# WIFI_Bluetooth.net
KiCad netlist of a schematic drawn in Altium Designer
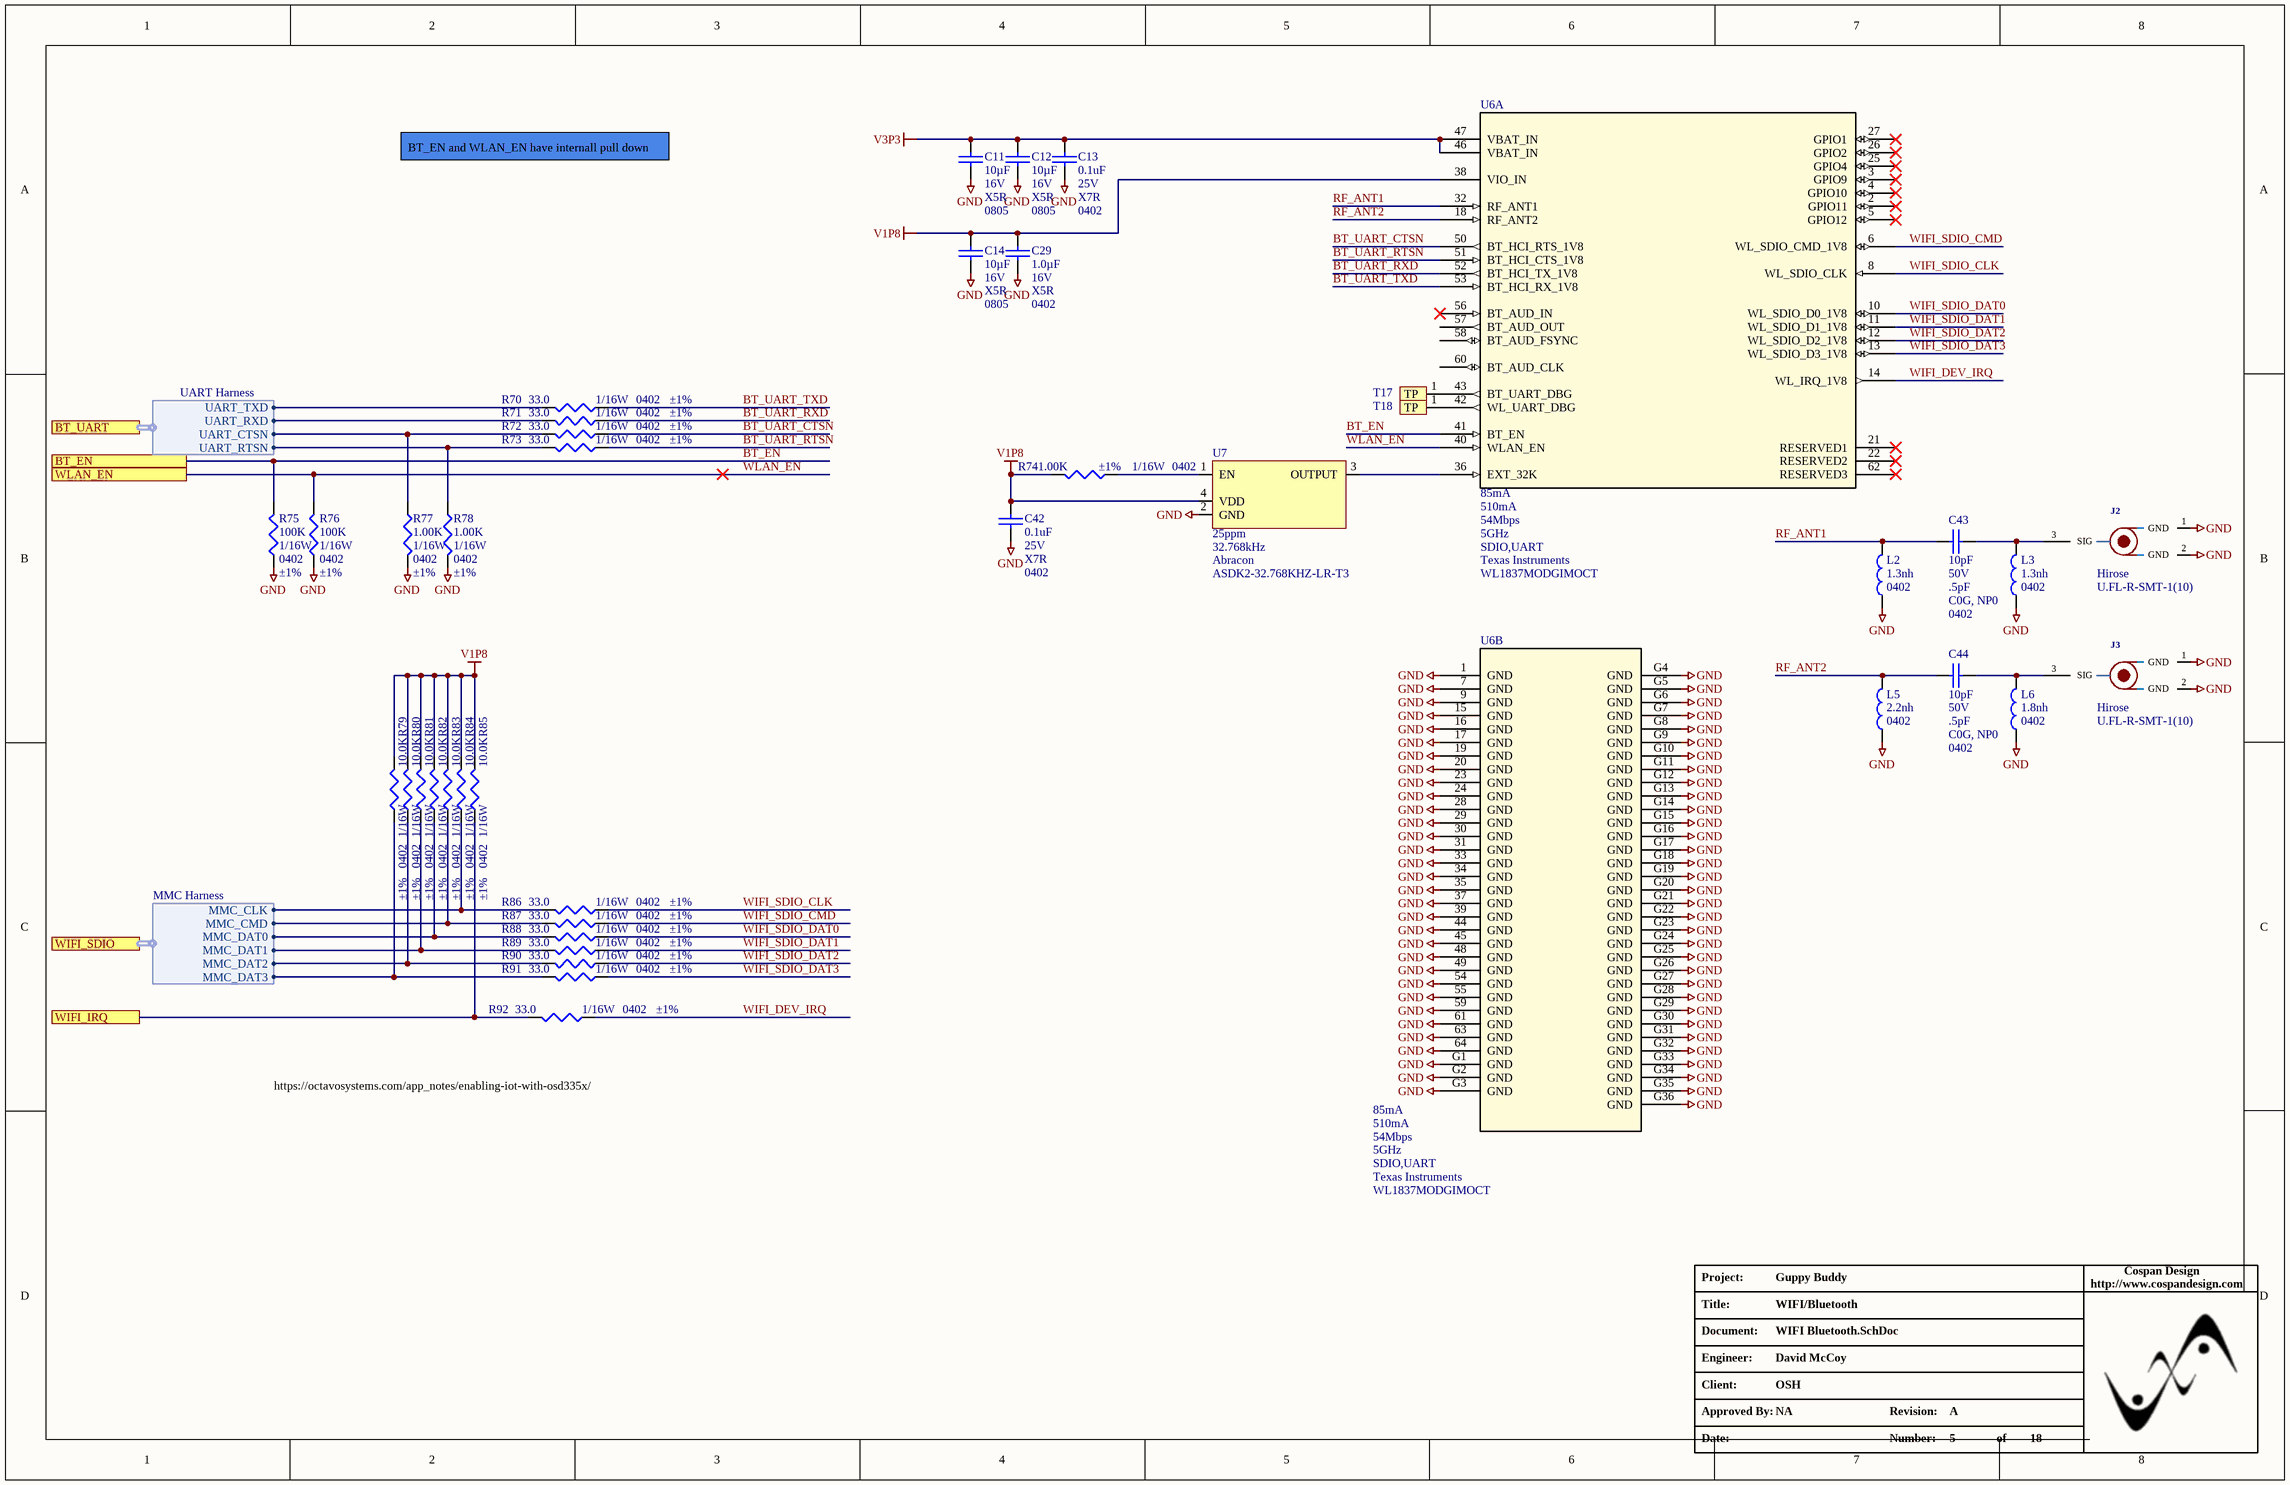
[diagram p0: WIFI Bluetooth.SchDoc]

(export (version "E")
  (design (tool "Eeschema 10.0.6"))
  (components
    (comp (ref "C11")
      (value "10µF")
      (footprint "C_ERA-0805")
      (description "CAP CER 10uF 16V X5R 20% 0805")
      (fields
        (field (name "MANUFACTURER") "Taiyo Yuden")
        (field (name "MANUFACTURER PART NUMBER") "EMK212BJ106KG-T")
        (field (name "CAPACITANCE") "10µF")
        (field (name "VOLTAGE - RATED") "16V")
        (field (name "TEMPERATURE COEFFICIENT") "X5R")
        (field (name "PACKAGE / CASE") "0805")
      )
      (libsource (lib "Main Library") (part "C_0805_10UF_16V"))
    )
    (comp (ref "C12")
      (value "10µF")
      (footprint "C_ERA-0805")
      (description "CAP CER 10uF 16V X5R 20% 0805")
      (fields
        (field (name "MANUFACTURER") "Taiyo Yuden")
        (field (name "MANUFACTURER PART NUMBER") "EMK212BJ106KG-T")
        (field (name "CAPACITANCE") "10µF")
        (field (name "VOLTAGE - RATED") "16V")
        (field (name "TEMPERATURE COEFFICIENT") "X5R")
        (field (name "PACKAGE / CASE") "0805")
      )
      (libsource (lib "Main Library") (part "C_0805_10UF_16V"))
    )
    (comp (ref "C13")
      (value "C_0402_0.1UF_25V")
      (footprint "C_0402")
      (description "CAP CER 0.1UF 25V X6S 0402")
      (fields
        (field (name "TOLERANCE") "10%")
        (field (name "CAPACITANCE") "0.1uF")
        (field (name "VOLTAGE - RATED") "25V")
        (field (name "TEMPERATURE COEFFICIENT") "X7R")
        (field (name "PACKAGE / CASE") "0402")
      )
      (libsource (lib "Cospan Design") (part "C_0402_0.1UF_25V"))
    )
    (comp (ref "C14")
      (value "10µF")
      (footprint "C_ERA-0805")
      (description "CAP CER 10uF 16V X5R 20% 0805")
      (fields
        (field (name "MANUFACTURER") "Taiyo Yuden")
        (field (name "MANUFACTURER PART NUMBER") "EMK212BJ106KG-T")
        (field (name "CAPACITANCE") "10µF")
        (field (name "VOLTAGE - RATED") "16V")
        (field (name "TEMPERATURE COEFFICIENT") "X5R")
        (field (name "PACKAGE / CASE") "0805")
      )
      (libsource (lib "Main Library") (part "C_0805_10UF_16V"))
    )
    (comp (ref "C29")
      (value "1.0uF")
      (footprint "C_0402")
      (description "CAP CER 1.0UF 16V X5R 0402")
      (fields
        (field (name "TOLERANCE") "10%")
        (field (name "CAPACITANCE") "1.0µF")
        (field (name "VOLTAGE - RATED") "16V")
        (field (name "TEMPERATURE COEFFICIENT") "X5R")
        (field (name "PACKAGE / CASE") "0402")
        (field (name "VOLTAGE") "16V")
      )
      (libsource (lib "Main LibraryX") (part "C_0402_1.0UF_16V"))
    )
    (comp (ref "C42")
      (value "C_0402_0.1UF_25V")
      (footprint "C_0402")
      (description "CAP CER 0.1UF 25V X6S 0402")
      (fields
        (field (name "TOLERANCE") "10%")
        (field (name "CAPACITANCE") "0.1uF")
        (field (name "VOLTAGE - RATED") "25V")
        (field (name "TEMPERATURE COEFFICIENT") "X7R")
        (field (name "PACKAGE / CASE") "0402")
      )
      (libsource (lib "Cospan Design") (part "C_0402_0.1UF_25V"))
    )
    (comp (ref "C43")
      (value "10pF")
      (footprint "C_0402")
      (description "CAP CER 10PF 50V NP0 0402")
      (fields
        (field (name "MANUFACTURER") "Taiyo Yuden")
        (field (name "MANUFACTURER PART NUMBER") "UMK105CG100DV-F")
        (field (name "CAPACITANCE") "10pF")
        (field (name "VOLTAGE - RATED") "50V")
        (field (name "TOLERANCE") ".5pF")
        (field (name "TEMPERATURE COEFFICIENT") "C0G, NP0")
        (field (name "PACKAGE / CASE") "0402")
      )
      (libsource (lib "Main Library") (part "C_0402_10PF_50V"))
    )
    (comp (ref "C44")
      (value "10pF")
      (footprint "C_ERA-0402")
      (description "CAP CER 10PF 50V NP0 0402")
      (fields
        (field (name "MANUFACTURER") "Taiyo Yuden")
        (field (name "MANUFACTURER PART NUMBER") "UMK105CG100DV-F")
        (field (name "CAPACITANCE") "10pF")
        (field (name "VOLTAGE - RATED") "50V")
        (field (name "TOLERANCE") ".5pF")
        (field (name "TEMPERATURE COEFFICIENT") "C0G, NP0")
        (field (name "PACKAGE / CASE") "0402")
      )
      (libsource (lib "Main Library") (part "C_0402_10PF_50V"))
    )
    (comp (ref "J2")
      (value "U.FL-R-SMT-1(10)")
      (footprint "U.FL-R-SMT-1")
      (description "CONN UMC JACK STR 50 OHM SMD")
      (fields
        (field (name "MANUFACTURER 1") "Hirose")
        (field (name "MANUFACTURER PART NUMBER 1") "U.FL-R-SMT-1(10)")
        (field (name "LIBRARYNAME") "GHI-Connectors")
      )
      (libsource (lib "Cospan Design") (part "J_U.FL-R-SMT-1"))
    )
    (comp (ref "J3")
      (value "U.FL-R-SMT-1(10)")
      (footprint "U.FL-R-SMT-1")
      (description "CONN UMC JACK STR 50 OHM SMD")
      (fields
        (field (name "MANUFACTURER 1") "Hirose")
        (field (name "MANUFACTURER PART NUMBER 1") "U.FL-R-SMT-1(10)")
        (field (name "LIBRARYNAME") "GHI-Connectors")
      )
      (libsource (lib "Cospan Design") (part "J_U.FL-R-SMT-1"))
    )
    (comp (ref "L2")
      (value "L_0402_1.3nH")
      (footprint "R_0402")
      (description "FIXED IND 1.3NH 1A 90 MOHM")
      (fields
        (field (name "TOLERANCE") "5%")
        (field (name "INDUCTANCE") "1.3nh")
        (field (name "CASE CODE (IMPERIAL)") "0402")
      )
      (libsource (lib "Cospan Design") (part "L_0402_1.3nH"))
    )
    (comp (ref "L3")
      (value "L_0402_1.3nH")
      (footprint "R_0402")
      (description "FIXED IND 1.3NH 1A 90 MOHM")
      (fields
        (field (name "TOLERANCE") "5%")
        (field (name "INDUCTANCE") "1.3nh")
        (field (name "CASE CODE (IMPERIAL)") "0402")
      )
      (libsource (lib "Cospan Design") (part "L_0402_1.3nH"))
    )
    (comp (ref "L5")
      (value "L_0402_2.2nH")
      (footprint "R_0402")
      (description "FIXED IND 2.2NH 950MA 150 MOHM")
      (fields (field (name "INDUCTANCE") "2.2nh") (field (name "CASE CODE (IMPERIAL)") "0402"))
      (libsource (lib "Cospan Design") (part "L_0402_2.2nH"))
    )
    (comp (ref "L6")
      (value "L_0402_1.8nH")
      (footprint "R_0402")
      (description "FIXED IND 1.8NH 950MA 100 MOHM")
      (fields (field (name "INDUCTANCE") "1.8nh") (field (name "CASE CODE (IMPERIAL)") "0402"))
      (libsource (lib "Cospan Design") (part "L_0402_1.8nH"))
    )
    (comp (ref "R70")
      (value "R_0402_33")
      (footprint "R_0402")
      (description "RES 33.0 OHM 1/16W 1% 0402 SMD")
      (fields
        (field (name "MANUFACTURER") "Yageo")
        (field (name "MANUFACTURER PART NUMBER") "RC0402FR-0733RL")
        (field (name "RESISTANCE IN OHMS") "33.0")
        (field (name "POWER (WATTS)") "1/16W")
        (field (name "CASE") "0402")
        (field (name "TOLERANCE") "±1%")
      )
      (libsource (lib "Main Library") (part "R_0402_33"))
    )
    (comp (ref "R71")
      (value "R_0402_33")
      (footprint "R_0402")
      (description "RES 33.0 OHM 1/16W 1% 0402 SMD")
      (fields
        (field (name "MANUFACTURER") "Yageo")
        (field (name "MANUFACTURER PART NUMBER") "RC0402FR-0733RL")
        (field (name "RESISTANCE IN OHMS") "33.0")
        (field (name "POWER (WATTS)") "1/16W")
        (field (name "CASE") "0402")
        (field (name "TOLERANCE") "±1%")
      )
      (libsource (lib "Main Library") (part "R_0402_33"))
    )
    (comp (ref "R72")
      (value "R_0402_33")
      (footprint "R_0402")
      (description "RES 33.0 OHM 1/16W 1% 0402 SMD")
      (fields
        (field (name "MANUFACTURER") "Yageo")
        (field (name "MANUFACTURER PART NUMBER") "RC0402FR-0733RL")
        (field (name "RESISTANCE IN OHMS") "33.0")
        (field (name "POWER (WATTS)") "1/16W")
        (field (name "CASE") "0402")
        (field (name "TOLERANCE") "±1%")
      )
      (libsource (lib "Main Library") (part "R_0402_33"))
    )
    (comp (ref "R73")
      (value "R_0402_33")
      (footprint "R_0402")
      (description "RES 33.0 OHM 1/16W 1% 0402 SMD")
      (fields
        (field (name "MANUFACTURER") "Yageo")
        (field (name "MANUFACTURER PART NUMBER") "RC0402FR-0733RL")
        (field (name "RESISTANCE IN OHMS") "33.0")
        (field (name "POWER (WATTS)") "1/16W")
        (field (name "CASE") "0402")
        (field (name "TOLERANCE") "±1%")
      )
      (libsource (lib "Main Library") (part "R_0402_33"))
    )
    (comp (ref "R74")
      (value "1.0k Ohms")
      (footprint "R_0402")
      (description "RES 1.00K OHM 1/16W 1% 0402 SMD")
      (fields
        (field (name "MANUFACTURER") "Yageo")
        (field (name "MANUFACTURER PART NUMBER") "RC0402FR-071KL")
        (field (name "RESISTANCE IN OHMS") "1.00K")
        (field (name "POWER (WATTS)") "1/16W")
        (field (name "CASE") "0402")
        (field (name "TOLERANCE") "±1%")
      )
      (libsource (lib "Main Library") (part "R_0402_1.0K"))
    )
    (comp (ref "R75")
      (value "R_0402_100.0K")
      (footprint "R_0402")
      (description "RES 100K OHM 1/16W 1% 0402 SMD")
      (fields
        (field (name "MANUFACTURER") "Stackpole Electronics Inc")
        (field (name "MANUFACTURER PART NUMBER") "RMCF0402FT100K")
        (field (name "RESISTANCE IN OHMS") "100K")
        (field (name "POWER (WATTS)") "1/16W")
        (field (name "CASE") "0402")
        (field (name "TOLERANCE") "±1%")
      )
      (libsource (lib "Main Library") (part "R_0402_100.0K"))
    )
    (comp (ref "R76")
      (value "R_0402_100.0K")
      (footprint "R_0402")
      (description "RES 100K OHM 1/16W 1% 0402 SMD")
      (fields
        (field (name "MANUFACTURER") "Stackpole Electronics Inc")
        (field (name "MANUFACTURER PART NUMBER") "RMCF0402FT100K")
        (field (name "RESISTANCE IN OHMS") "100K")
        (field (name "POWER (WATTS)") "1/16W")
        (field (name "CASE") "0402")
        (field (name "TOLERANCE") "±1%")
      )
      (libsource (lib "Main Library") (part "R_0402_100.0K"))
    )
    (comp (ref "R77")
      (value "1.0k Ohms")
      (footprint "R_0402")
      (description "RES 1.00K OHM 1/16W 1% 0402 SMD")
      (fields
        (field (name "MANUFACTURER") "Yageo")
        (field (name "MANUFACTURER PART NUMBER") "RC0402FR-071KL")
        (field (name "RESISTANCE IN OHMS") "1.00K")
        (field (name "POWER (WATTS)") "1/16W")
        (field (name "CASE") "0402")
        (field (name "TOLERANCE") "±1%")
      )
      (libsource (lib "Main Library") (part "R_0402_1.0K"))
    )
    (comp (ref "R78")
      (value "1.0k Ohms")
      (footprint "R_0402")
      (description "RES 1.00K OHM 1/16W 1% 0402 SMD")
      (fields
        (field (name "MANUFACTURER") "Yageo")
        (field (name "MANUFACTURER PART NUMBER") "RC0402FR-071KL")
        (field (name "RESISTANCE IN OHMS") "1.00K")
        (field (name "POWER (WATTS)") "1/16W")
        (field (name "CASE") "0402")
        (field (name "TOLERANCE") "±1%")
      )
      (libsource (lib "Main Library") (part "R_0402_1.0K"))
    )
    (comp (ref "R79")
      (value "R_0402_10.0K")
      (footprint "R_0402")
      (description "RES 10.0K OHM 1/16W 1% 0402 SMD")
      (fields
        (field (name "MANUFACTURER") "Stackpole Electronics Inc")
        (field (name "MANUFACTURER PART NUMBER") "RMCF0402FT10K0")
        (field (name "RESISTANCE IN OHMS") "10.0K")
        (field (name "POWER (WATTS)") "1/16W")
        (field (name "CASE") "0402")
        (field (name "TOLERANCE") "±1%")
      )
      (libsource (lib "Cospan Design") (part "R_0402_10.0K"))
    )
    (comp (ref "R80")
      (value "R_0402_10.0K")
      (footprint "R_0402")
      (description "RES 10.0K OHM 1/16W 1% 0402 SMD")
      (fields
        (field (name "MANUFACTURER") "Stackpole Electronics Inc")
        (field (name "MANUFACTURER PART NUMBER") "RMCF0402FT10K0")
        (field (name "RESISTANCE IN OHMS") "10.0K")
        (field (name "POWER (WATTS)") "1/16W")
        (field (name "CASE") "0402")
        (field (name "TOLERANCE") "±1%")
      )
      (libsource (lib "Cospan Design") (part "R_0402_10.0K"))
    )
    (comp (ref "R81")
      (value "R_0402_10.0K")
      (footprint "R_0402")
      (description "RES 10.0K OHM 1/16W 1% 0402 SMD")
      (fields
        (field (name "MANUFACTURER") "Stackpole Electronics Inc")
        (field (name "MANUFACTURER PART NUMBER") "RMCF0402FT10K0")
        (field (name "RESISTANCE IN OHMS") "10.0K")
        (field (name "POWER (WATTS)") "1/16W")
        (field (name "CASE") "0402")
        (field (name "TOLERANCE") "±1%")
      )
      (libsource (lib "Cospan Design") (part "R_0402_10.0K"))
    )
    (comp (ref "R82")
      (value "R_0402_10.0K")
      (footprint "R_0402")
      (description "RES 10.0K OHM 1/16W 1% 0402 SMD")
      (fields
        (field (name "MANUFACTURER") "Stackpole Electronics Inc")
        (field (name "MANUFACTURER PART NUMBER") "RMCF0402FT10K0")
        (field (name "RESISTANCE IN OHMS") "10.0K")
        (field (name "POWER (WATTS)") "1/16W")
        (field (name "CASE") "0402")
        (field (name "TOLERANCE") "±1%")
      )
      (libsource (lib "Cospan Design") (part "R_0402_10.0K"))
    )
    (comp (ref "R83")
      (value "R_0402_10.0K")
      (footprint "R_0402")
      (description "RES 10.0K OHM 1/16W 1% 0402 SMD")
      (fields
        (field (name "MANUFACTURER") "Stackpole Electronics Inc")
        (field (name "MANUFACTURER PART NUMBER") "RMCF0402FT10K0")
        (field (name "RESISTANCE IN OHMS") "10.0K")
        (field (name "POWER (WATTS)") "1/16W")
        (field (name "CASE") "0402")
        (field (name "TOLERANCE") "±1%")
      )
      (libsource (lib "Cospan Design") (part "R_0402_10.0K"))
    )
    (comp (ref "R84")
      (value "R_0402_10.0K")
      (footprint "R_0402")
      (description "RES 10.0K OHM 1/16W 1% 0402 SMD")
      (fields
        (field (name "MANUFACTURER") "Stackpole Electronics Inc")
        (field (name "MANUFACTURER PART NUMBER") "RMCF0402FT10K0")
        (field (name "RESISTANCE IN OHMS") "10.0K")
        (field (name "POWER (WATTS)") "1/16W")
        (field (name "CASE") "0402")
        (field (name "TOLERANCE") "±1%")
      )
      (libsource (lib "Cospan Design") (part "R_0402_10.0K"))
    )
    (comp (ref "R85")
      (value "R_0402_10.0K")
      (footprint "R_0402")
      (description "RES 10.0K OHM 1/16W 1% 0402 SMD")
      (fields
        (field (name "MANUFACTURER") "Stackpole Electronics Inc")
        (field (name "MANUFACTURER PART NUMBER") "RMCF0402FT10K0")
        (field (name "RESISTANCE IN OHMS") "10.0K")
        (field (name "POWER (WATTS)") "1/16W")
        (field (name "CASE") "0402")
        (field (name "TOLERANCE") "±1%")
      )
      (libsource (lib "Cospan Design") (part "R_0402_10.0K"))
    )
    (comp (ref "R86")
      (value "R_0402_33")
      (footprint "R_0402")
      (description "RES 33.0 OHM 1/16W 1% 0402 SMD")
      (fields
        (field (name "MANUFACTURER") "Yageo")
        (field (name "MANUFACTURER PART NUMBER") "RC0402FR-0733RL")
        (field (name "RESISTANCE IN OHMS") "33.0")
        (field (name "POWER (WATTS)") "1/16W")
        (field (name "CASE") "0402")
        (field (name "TOLERANCE") "±1%")
      )
      (libsource (lib "Main Library") (part "R_0402_33"))
    )
    (comp (ref "R87")
      (value "R_0402_33")
      (footprint "R_0402")
      (description "RES 33.0 OHM 1/16W 1% 0402 SMD")
      (fields
        (field (name "MANUFACTURER") "Yageo")
        (field (name "MANUFACTURER PART NUMBER") "RC0402FR-0733RL")
        (field (name "RESISTANCE IN OHMS") "33.0")
        (field (name "POWER (WATTS)") "1/16W")
        (field (name "CASE") "0402")
        (field (name "TOLERANCE") "±1%")
      )
      (libsource (lib "Main Library") (part "R_0402_33"))
    )
    (comp (ref "R88")
      (value "R_0402_33")
      (footprint "R_0402")
      (description "RES 33.0 OHM 1/16W 1% 0402 SMD")
      (fields
        (field (name "MANUFACTURER") "Yageo")
        (field (name "MANUFACTURER PART NUMBER") "RC0402FR-0733RL")
        (field (name "RESISTANCE IN OHMS") "33.0")
        (field (name "POWER (WATTS)") "1/16W")
        (field (name "CASE") "0402")
        (field (name "TOLERANCE") "±1%")
      )
      (libsource (lib "Main Library") (part "R_0402_33"))
    )
    (comp (ref "R89")
      (value "R_0402_33")
      (footprint "R_0402")
      (description "RES 33.0 OHM 1/16W 1% 0402 SMD")
      (fields
        (field (name "MANUFACTURER") "Yageo")
        (field (name "MANUFACTURER PART NUMBER") "RC0402FR-0733RL")
        (field (name "RESISTANCE IN OHMS") "33.0")
        (field (name "POWER (WATTS)") "1/16W")
        (field (name "CASE") "0402")
        (field (name "TOLERANCE") "±1%")
      )
      (libsource (lib "Main Library") (part "R_0402_33"))
    )
    (comp (ref "R90")
      (value "R_0402_33")
      (footprint "R_0402")
      (description "RES 33.0 OHM 1/16W 1% 0402 SMD")
      (fields
        (field (name "MANUFACTURER") "Yageo")
        (field (name "MANUFACTURER PART NUMBER") "RC0402FR-0733RL")
        (field (name "RESISTANCE IN OHMS") "33.0")
        (field (name "POWER (WATTS)") "1/16W")
        (field (name "CASE") "0402")
        (field (name "TOLERANCE") "±1%")
      )
      (libsource (lib "Main Library") (part "R_0402_33"))
    )
    (comp (ref "R91")
      (value "R_0402_33")
      (footprint "R_0402")
      (description "RES 33.0 OHM 1/16W 1% 0402 SMD")
      (fields
        (field (name "MANUFACTURER") "Yageo")
        (field (name "MANUFACTURER PART NUMBER") "RC0402FR-0733RL")
        (field (name "RESISTANCE IN OHMS") "33.0")
        (field (name "POWER (WATTS)") "1/16W")
        (field (name "CASE") "0402")
        (field (name "TOLERANCE") "±1%")
      )
      (libsource (lib "Main Library") (part "R_0402_33"))
    )
    (comp (ref "R92")
      (value "R_0402_33")
      (footprint "R_0402")
      (description "RES 33.0 OHM 1/16W 1% 0402 SMD")
      (fields
        (field (name "MANUFACTURER") "Yageo")
        (field (name "MANUFACTURER PART NUMBER") "RC0402FR-0733RL")
        (field (name "RESISTANCE IN OHMS") "33.0")
        (field (name "POWER (WATTS)") "1/16W")
        (field (name "CASE") "0402")
        (field (name "TOLERANCE") "±1%")
      )
      (libsource (lib "Main Library") (part "R_0402_33"))
    )
    (comp (ref "T17")
      (value "TEST_POINT_SMALL")
      (footprint "TestPointSmall")
      (description "OSCILLOSCOPE TEST POINT")
      (libsource (lib "Main LibraryX") (part "TEST_POINT_SMALL"))
    )
    (comp (ref "T18")
      (value "TEST_POINT_SMALL")
      (footprint "TestPointSmall")
      (description "OSCILLOSCOPE TEST POINT")
      (libsource (lib "Main LibraryX") (part "TEST_POINT_SMALL"))
    )
    (comp (ref "U6")
      (value "U_WL1837MODGIMOCT")
      (footprint "MOC0100A")
      (description "WiLink Wi-Fi 2.4/5GHz MIMO BT/BLE")
      (fields
        (field (name "CURRENT - RECEIVING") "85mA")
        (field (name "CURRENT - TRANSMITTING") "510mA")
        (field (name "DATA RATE") "54Mbps")
        (field (name "FREQUENCY") "5GHz")
        (field (name "INTERFACE") "SDIO,UART")
        (field (name "MANUFACTURER 1") "Texas Instruments")
        (field (name "MANUFACTURER PART NUMBER 1") "WL1837MODGIMOCT")
      )
      (libsource (lib "Cospan Design") (part "U_WL1837MODGIMOCT"))
    )
    (comp (ref "U7")
      (value "U_ASDK2-32.768KHZ-LR-T3")
      (footprint "KC2520B")
      (description "32.768kHz CMOS XO (Standard) Oscillator Surface Mount 1.8V 1.5mA Enable/Disable")
      (fields
        (field (name "FREQUENCY STABILITY") "25ppm")
        (field (name "FREQUENCY") "32.768kHz")
        (field (name "MANUFACTURER 1") "Abracon")
        (field (name "MANUFACTURER PART NUMBER 1") "ASDK2-32.768KHZ-LR-T3")
      )
      (libsource (lib "Cospan Design") (part "U_ASDK2-32.768KHZ-LR-T3"))
    )
  )
  (nets
    (net (code "4") (name "/BT_EN") (class "Default")
      (node (ref "R75") (pin "1") (pinfunction "1_1") (pintype "passive"))
      (node (ref "U6") (pin "41") (pinfunction "BT_EN_41") (pintype "input"))
    )
    (net (code "5") (name "/BT_UART_CTSN") (class "Default")
      (node (ref "R72") (pin "2") (pinfunction "2_2") (pintype "passive"))
      (node (ref "U6") (pin "50") (pinfunction "BT_HCI_RTS_1V8_50") (pintype "output"))
    )
    (net (code "6") (name "/BT_UART_RTSN") (class "Default")
      (node (ref "R73") (pin "2") (pinfunction "2_2") (pintype "passive"))
      (node (ref "U6") (pin "51") (pinfunction "BT_HCI_CTS_1V8_51") (pintype "input"))
    )
    (net (code "7") (name "/BT_UART_RXD") (class "Default")
      (node (ref "R71") (pin "2") (pinfunction "2_2") (pintype "passive"))
      (node (ref "U6") (pin "52") (pinfunction "BT_HCI_TX_1V8_52") (pintype "output"))
    )
    (net (code "8") (name "/BT_UART_TXD") (class "Default")
      (node (ref "R70") (pin "2") (pinfunction "2_2") (pintype "passive"))
      (node (ref "U6") (pin "53") (pinfunction "BT_HCI_RX_1V8_53") (pintype "input"))
    )
    (net (code "9") (name "/MMC_CLK") (class "Default")
      (node (ref "R84") (pin "2") (pinfunction "2_2") (pintype "passive"))
      (node (ref "R86") (pin "1") (pinfunction "1_1") (pintype "passive"))
    )
    (net (code "10") (name "/MMC_CMD") (class "Default")
      (node (ref "R83") (pin "2") (pinfunction "2_2") (pintype "passive"))
      (node (ref "R87") (pin "1") (pinfunction "1_1") (pintype "passive"))
    )
    (net (code "11") (name "/MMC_DAT0") (class "Default")
      (node (ref "R82") (pin "2") (pinfunction "2_2") (pintype "passive"))
      (node (ref "R88") (pin "1") (pinfunction "1_1") (pintype "passive"))
    )
    (net (code "12") (name "/MMC_DAT1") (class "Default")
      (node (ref "R81") (pin "2") (pinfunction "2_2") (pintype "passive"))
      (node (ref "R89") (pin "1") (pinfunction "1_1") (pintype "passive"))
    )
    (net (code "13") (name "/MMC_DAT2") (class "Default")
      (node (ref "R80") (pin "2") (pinfunction "2_2") (pintype "passive"))
      (node (ref "R90") (pin "1") (pinfunction "1_1") (pintype "passive"))
    )
    (net (code "14") (name "/MMC_DAT3") (class "Default")
      (node (ref "R79") (pin "2") (pinfunction "2_2") (pintype "passive"))
      (node (ref "R91") (pin "1") (pinfunction "1_1") (pintype "passive"))
    )
    (net (code "15") (name "/RF_ANT1") (class "Default")
      (node (ref "C43") (pin "2") (pinfunction "2_2") (pintype "passive"))
      (node (ref "L2") (pin "2") (pintype "passive"))
      (node (ref "U6") (pin "32") (pinfunction "RF_ANT1_32") (pintype "input"))
    )
    (net (code "16") (name "/RF_ANT2") (class "Default")
      (node (ref "C44") (pin "2") (pinfunction "2_2") (pintype "passive"))
      (node (ref "L5") (pin "2") (pintype "passive"))
      (node (ref "U6") (pin "18") (pinfunction "RF_ANT2_18") (pintype "input"))
    )
    (net (code "17") (name "/UART_CTSN") (class "Default")
      (node (ref "R72") (pin "1") (pinfunction "1_1") (pintype "passive"))
      (node (ref "R77") (pin "2") (pinfunction "2_2") (pintype "passive"))
    )
    (net (code "18") (name "/UART_RTSN") (class "Default")
      (node (ref "R73") (pin "1") (pinfunction "1_1") (pintype "passive"))
      (node (ref "R78") (pin "2") (pinfunction "2_2") (pintype "passive"))
    )
    (net (code "19") (name "/UART_RXD") (class "Default")
      (node (ref "R71") (pin "1") (pinfunction "1_1") (pintype "passive"))
    )
    (net (code "20") (name "/UART_TXD") (class "Default")
      (node (ref "R70") (pin "1") (pinfunction "1_1") (pintype "passive"))
    )
    (net (code "21") (name "/WIFI_DEV_IRQ") (class "Default")
      (node (ref "R92") (pin "2") (pinfunction "2_2") (pintype "passive"))
      (node (ref "U6") (pin "14") (pinfunction "WL_IRQ_1V8_14") (pintype "output"))
    )
    (net (code "22") (name "/WIFI_IRQ") (class "Default")
      (node (ref "R85") (pin "2") (pinfunction "2_2") (pintype "passive"))
      (node (ref "R92") (pin "1") (pinfunction "1_1") (pintype "passive"))
    )
    (net (code "23") (name "/WIFI_SDIO_CLK") (class "Default")
      (node (ref "R86") (pin "2") (pinfunction "2_2") (pintype "passive"))
      (node (ref "U6") (pin "8") (pinfunction "WL_SDIO_CLK_8") (pintype "input"))
    )
    (net (code "24") (name "/WIFI_SDIO_CMD") (class "Default")
      (node (ref "R87") (pin "2") (pinfunction "2_2") (pintype "passive"))
      (node (ref "U6") (pin "6") (pinfunction "WL_SDIO_CMD_1V8_6") (pintype "bidirectional"))
    )
    (net (code "25") (name "/WIFI_SDIO_DAT0") (class "Default")
      (node (ref "R88") (pin "2") (pinfunction "2_2") (pintype "passive"))
      (node (ref "U6") (pin "10") (pinfunction "WL_SDIO_D0_1V8_10") (pintype "bidirectional"))
    )
    (net (code "26") (name "/WIFI_SDIO_DAT1") (class "Default")
      (node (ref "R89") (pin "2") (pinfunction "2_2") (pintype "passive"))
      (node (ref "U6") (pin "11") (pinfunction "WL_SDIO_D1_1V8_11") (pintype "bidirectional"))
    )
    (net (code "27") (name "/WIFI_SDIO_DAT2") (class "Default")
      (node (ref "R90") (pin "2") (pinfunction "2_2") (pintype "passive"))
      (node (ref "U6") (pin "12") (pinfunction "WL_SDIO_D2_1V8_12") (pintype "bidirectional"))
    )
    (net (code "28") (name "/WIFI_SDIO_DAT3") (class "Default")
      (node (ref "R91") (pin "2") (pinfunction "2_2") (pintype "passive"))
      (node (ref "U6") (pin "13") (pinfunction "WL_SDIO_D3_1V8_13") (pintype "bidirectional"))
    )
    (net (code "29") (name "/WLAN_EN") (class "Default")
      (node (ref "R76") (pin "1") (pinfunction "1_1") (pintype "passive"))
      (node (ref "U6") (pin "40") (pinfunction "WLAN_EN_40") (pintype "input"))
    )
    (net (code "32") (name "GND") (class "Default")
      (node (ref "C11") (pin "1") (pinfunction "1_1") (pintype "passive"))
      (node (ref "C12") (pin "1") (pinfunction "1_1") (pintype "passive"))
      (node (ref "C13") (pin "1") (pinfunction "1_1") (pintype "passive"))
      (node (ref "C14") (pin "1") (pinfunction "1_1") (pintype "passive"))
      (node (ref "C29") (pin "1") (pinfunction "1_1") (pintype "passive"))
      (node (ref "C42") (pin "1") (pinfunction "1_1") (pintype "passive"))
      (node (ref "J2") (pin "1") (pinfunction "GND_1") (pintype "passive"))
      (node (ref "J2") (pin "2") (pinfunction "GND_2") (pintype "passive"))
      (node (ref "J3") (pin "1") (pinfunction "GND_1") (pintype "passive"))
      (node (ref "J3") (pin "2") (pinfunction "GND_2") (pintype "passive"))
      (node (ref "L2") (pin "1") (pintype "passive"))
      (node (ref "L3") (pin "1") (pintype "passive"))
      (node (ref "L5") (pin "1") (pintype "passive"))
      (node (ref "L6") (pin "1") (pintype "passive"))
      (node (ref "R75") (pin "2") (pinfunction "2_2") (pintype "passive"))
      (node (ref "R76") (pin "2") (pinfunction "2_2") (pintype "passive"))
      (node (ref "R77") (pin "1") (pinfunction "1_1") (pintype "passive"))
      (node (ref "R78") (pin "1") (pinfunction "1_1") (pintype "passive"))
      (node (ref "U6") (pin "1") (pinfunction "GND_1") (pintype "power_in"))
      (node (ref "U6") (pin "15") (pinfunction "GND_15") (pintype "power_in"))
      (node (ref "U6") (pin "16") (pinfunction "GND_16") (pintype "power_in"))
      (node (ref "U6") (pin "17") (pinfunction "GND_17") (pintype "power_in"))
      (node (ref "U6") (pin "19") (pinfunction "GND_19") (pintype "power_in"))
      (node (ref "U6") (pin "20") (pinfunction "GND_20") (pintype "power_in"))
      (node (ref "U6") (pin "23") (pinfunction "GND_23") (pintype "power_in"))
      (node (ref "U6") (pin "24") (pinfunction "GND_24") (pintype "power_in"))
      (node (ref "U6") (pin "28") (pinfunction "GND_28") (pintype "power_in"))
      (node (ref "U6") (pin "29") (pinfunction "GND_29") (pintype "power_in"))
      (node (ref "U6") (pin "30") (pinfunction "GND_30") (pintype "power_in"))
      (node (ref "U6") (pin "31") (pinfunction "GND_31") (pintype "power_in"))
      (node (ref "U6") (pin "33") (pinfunction "GND_33") (pintype "power_in"))
      (node (ref "U6") (pin "34") (pinfunction "GND_34") (pintype "power_in"))
      (node (ref "U6") (pin "35") (pinfunction "GND_35") (pintype "power_in"))
      (node (ref "U6") (pin "37") (pinfunction "GND_37") (pintype "power_in"))
      (node (ref "U6") (pin "39") (pinfunction "GND_39") (pintype "power_in"))
      (node (ref "U6") (pin "44") (pinfunction "GND_44") (pintype "power_in"))
      (node (ref "U6") (pin "45") (pinfunction "GND_45") (pintype "power_in"))
      (node (ref "U6") (pin "48") (pinfunction "GND_48") (pintype "power_in"))
      (node (ref "U6") (pin "49") (pinfunction "GND_49") (pintype "power_in"))
      (node (ref "U6") (pin "54") (pinfunction "GND_54") (pintype "power_in"))
      (node (ref "U6") (pin "55") (pinfunction "GND_55") (pintype "power_in"))
      (node (ref "U6") (pin "59") (pinfunction "GND_59") (pintype "power_in"))
      (node (ref "U6") (pin "61") (pinfunction "GND_61") (pintype "power_in"))
      (node (ref "U6") (pin "63") (pinfunction "GND_63") (pintype "power_in"))
      (node (ref "U6") (pin "64") (pinfunction "GND_64") (pintype "power_in"))
      (node (ref "U6") (pin "7") (pinfunction "GND_7") (pintype "power_in"))
      (node (ref "U6") (pin "9") (pinfunction "GND_9") (pintype "power_in"))
      (node (ref "U6") (pin "G1") (pinfunction "GND_G1") (pintype "power_in"))
      (node (ref "U6") (pin "G10") (pinfunction "GND_G10") (pintype "power_in"))
      (node (ref "U6") (pin "G11") (pinfunction "GND_G11") (pintype "power_in"))
      (node (ref "U6") (pin "G12") (pinfunction "GND_G12") (pintype "power_in"))
      (node (ref "U6") (pin "G13") (pinfunction "GND_G13") (pintype "power_in"))
      (node (ref "U6") (pin "G14") (pinfunction "GND_G14") (pintype "power_in"))
      (node (ref "U6") (pin "G15") (pinfunction "GND_G15") (pintype "power_in"))
      (node (ref "U6") (pin "G16") (pinfunction "GND_G16") (pintype "power_in"))
      (node (ref "U6") (pin "G17") (pinfunction "GND_G17") (pintype "power_in"))
      (node (ref "U6") (pin "G18") (pinfunction "GND_G18") (pintype "power_in"))
      (node (ref "U6") (pin "G19") (pinfunction "GND_G19") (pintype "power_in"))
      (node (ref "U6") (pin "G2") (pinfunction "GND_G2") (pintype "power_in"))
      (node (ref "U6") (pin "G20") (pinfunction "GND_G20") (pintype "power_in"))
      (node (ref "U6") (pin "G21") (pinfunction "GND_G21") (pintype "power_in"))
      (node (ref "U6") (pin "G22") (pinfunction "GND_G22") (pintype "power_in"))
      (node (ref "U6") (pin "G23") (pinfunction "GND_G23") (pintype "power_in"))
      (node (ref "U6") (pin "G24") (pinfunction "GND_G24") (pintype "power_in"))
      (node (ref "U6") (pin "G25") (pinfunction "GND_G25") (pintype "power_in"))
      (node (ref "U6") (pin "G26") (pinfunction "GND_G26") (pintype "power_in"))
      (node (ref "U6") (pin "G27") (pinfunction "GND_G27") (pintype "power_in"))
      (node (ref "U6") (pin "G28") (pinfunction "GND_G28") (pintype "power_in"))
      (node (ref "U6") (pin "G29") (pinfunction "GND_G29") (pintype "power_in"))
      (node (ref "U6") (pin "G3") (pinfunction "GND_G3") (pintype "power_in"))
      (node (ref "U6") (pin "G30") (pinfunction "GND_G30") (pintype "power_in"))
      (node (ref "U6") (pin "G31") (pinfunction "GND_G31") (pintype "power_in"))
      (node (ref "U6") (pin "G32") (pinfunction "GND_G32") (pintype "power_in"))
      (node (ref "U6") (pin "G33") (pinfunction "GND_G33") (pintype "power_in"))
      (node (ref "U6") (pin "G34") (pinfunction "GND_G34") (pintype "power_in"))
      (node (ref "U6") (pin "G35") (pinfunction "GND_G35") (pintype "power_in"))
      (node (ref "U6") (pin "G36") (pinfunction "GND_G36") (pintype "power_in"))
      (node (ref "U6") (pin "G4") (pinfunction "GND_G4") (pintype "power_in"))
      (node (ref "U6") (pin "G5") (pinfunction "GND_G5") (pintype "power_in"))
      (node (ref "U6") (pin "G6") (pinfunction "GND_G6") (pintype "power_in"))
      (node (ref "U6") (pin "G7") (pinfunction "GND_G7") (pintype "power_in"))
      (node (ref "U6") (pin "G8") (pinfunction "GND_G8") (pintype "power_in"))
      (node (ref "U6") (pin "G9") (pinfunction "GND_G9") (pintype "power_in"))
      (node (ref "U7") (pin "2") (pinfunction "GND_2") (pintype "passive"))
    )
    (net (code "33") (name "Net-(J2-SIG)") (class "Default")
      (node (ref "C43") (pin "1") (pinfunction "1_1") (pintype "passive"))
      (node (ref "J2") (pin "3") (pinfunction "SIG_3") (pintype "passive"))
      (node (ref "L3") (pin "2") (pintype "passive"))
    )
    (net (code "34") (name "Net-(J3-SIG)") (class "Default")
      (node (ref "C44") (pin "1") (pinfunction "1_1") (pintype "passive"))
      (node (ref "J3") (pin "3") (pinfunction "SIG_3") (pintype "passive"))
      (node (ref "L6") (pin "2") (pintype "passive"))
    )
    (net (code "35") (name "Net-(T17-TP)") (class "Default")
      (node (ref "T17") (pin "1") (pinfunction "TP_1") (pintype "passive"))
      (node (ref "U6") (pin "43") (pinfunction "BT_UART_DBG_43") (pintype "output"))
    )
    (net (code "36") (name "Net-(T18-TP)") (class "Default")
      (node (ref "T18") (pin "1") (pinfunction "TP_1") (pintype "passive"))
      (node (ref "U6") (pin "42") (pinfunction "WL_UART_DBG_42") (pintype "output"))
    )
    (net (code "37") (name "Net-(U6A-EXT_32K)") (class "Default")
      (node (ref "U6") (pin "36") (pinfunction "EXT_32K_36") (pintype "input"))
      (node (ref "U7") (pin "3") (pinfunction "OUTPUT_3") (pintype "passive"))
    )
    (net (code "38") (name "Net-(U7-EN)") (class "Default")
      (node (ref "R74") (pin "2") (pinfunction "2_2") (pintype "passive"))
      (node (ref "U7") (pin "1") (pinfunction "EN_1") (pintype "passive"))
    )
    (net (code "39") (name "V1P8") (class "Default")
      (node (ref "C14") (pin "2") (pinfunction "2_2") (pintype "passive"))
      (node (ref "C29") (pin "2") (pinfunction "2_2") (pintype "passive"))
      (node (ref "C42") (pin "2") (pinfunction "2_2") (pintype "passive"))
      (node (ref "R74") (pin "1") (pinfunction "1_1") (pintype "passive"))
      (node (ref "R79") (pin "1") (pinfunction "1_1") (pintype "passive"))
      (node (ref "R80") (pin "1") (pinfunction "1_1") (pintype "passive"))
      (node (ref "R81") (pin "1") (pinfunction "1_1") (pintype "passive"))
      (node (ref "R82") (pin "1") (pinfunction "1_1") (pintype "passive"))
      (node (ref "R83") (pin "1") (pinfunction "1_1") (pintype "passive"))
      (node (ref "R84") (pin "1") (pinfunction "1_1") (pintype "passive"))
      (node (ref "R85") (pin "1") (pinfunction "1_1") (pintype "passive"))
      (node (ref "U6") (pin "38") (pinfunction "VIO_IN_38") (pintype "power_in"))
      (node (ref "U7") (pin "4") (pinfunction "VDD_4") (pintype "passive"))
    )
    (net (code "40") (name "V3P3") (class "Default")
      (node (ref "C11") (pin "2") (pinfunction "2_2") (pintype "passive"))
      (node (ref "C12") (pin "2") (pinfunction "2_2") (pintype "passive"))
      (node (ref "C13") (pin "2") (pinfunction "2_2") (pintype "passive"))
      (node (ref "U6") (pin "46") (pinfunction "VBAT_IN_46") (pintype "power_in"))
      (node (ref "U6") (pin "47") (pinfunction "VBAT_IN_47") (pintype "power_in"))
    )
    (net (code "41") (name "unconnected-(U6A-BT_AUD_CLK-Pad60)") (class "Default")
      (node (ref "U6") (pin "60") (pinfunction "BT_AUD_CLK_60") (pintype "bidirectional"))
    )
    (net (code "42") (name "unconnected-(U6A-BT_AUD_FSYNC-Pad58)") (class "Default")
      (node (ref "U6") (pin "58") (pinfunction "BT_AUD_FSYNC_58") (pintype "bidirectional"))
    )
    (net (code "43") (name "unconnected-(U6A-BT_AUD_IN-Pad56)") (class "Default")
      (node (ref "U6") (pin "56") (pinfunction "BT_AUD_IN_56") (pintype "input+no_connect"))
    )
    (net (code "44") (name "unconnected-(U6A-BT_AUD_OUT-Pad57)") (class "Default")
      (node (ref "U6") (pin "57") (pinfunction "BT_AUD_OUT_57") (pintype "output"))
    )
    (net (code "45") (name "unconnected-(U6A-GPIO1-Pad27)") (class "Default")
      (node (ref "U6") (pin "27") (pinfunction "GPIO1_27") (pintype "bidirectional+no_connect"))
    )
    (net (code "46") (name "unconnected-(U6A-GPIO2-Pad26)") (class "Default")
      (node (ref "U6") (pin "26") (pinfunction "GPIO2_26") (pintype "bidirectional+no_connect"))
    )
    (net (code "47") (name "unconnected-(U6A-GPIO4-Pad25)") (class "Default")
      (node (ref "U6") (pin "25") (pinfunction "GPIO4_25") (pintype "bidirectional+no_connect"))
    )
    (net (code "48") (name "unconnected-(U6A-GPIO9-Pad3)") (class "Default")
      (node (ref "U6") (pin "3") (pinfunction "GPIO9_3") (pintype "bidirectional+no_connect"))
    )
    (net (code "49") (name "unconnected-(U6A-GPIO10-Pad4)") (class "Default")
      (node (ref "U6") (pin "4") (pinfunction "GPIO10_4") (pintype "bidirectional+no_connect"))
    )
    (net (code "50") (name "unconnected-(U6A-GPIO11-Pad2)") (class "Default")
      (node (ref "U6") (pin "2") (pinfunction "GPIO11_2") (pintype "bidirectional+no_connect"))
    )
    (net (code "51") (name "unconnected-(U6A-GPIO12-Pad5)") (class "Default")
      (node (ref "U6") (pin "5") (pinfunction "GPIO12_5") (pintype "bidirectional+no_connect"))
    )
    (net (code "52") (name "unconnected-(U6A-RESERVED1-Pad21)") (class "Default")
      (node (ref "U6") (pin "21") (pinfunction "RESERVED1_21") (pintype "passive+no_connect"))
    )
    (net (code "53") (name "unconnected-(U6A-RESERVED2-Pad22)") (class "Default")
      (node (ref "U6") (pin "22") (pinfunction "RESERVED2_22") (pintype "passive+no_connect"))
    )
    (net (code "54") (name "unconnected-(U6A-RESERVED3-Pad62)") (class "Default")
      (node (ref "U6") (pin "62") (pinfunction "RESERVED3_62") (pintype "passive+no_connect"))
    )
  )
)
